# powercommander.net
KiCad netlist of a schematic drawn in EAGLE
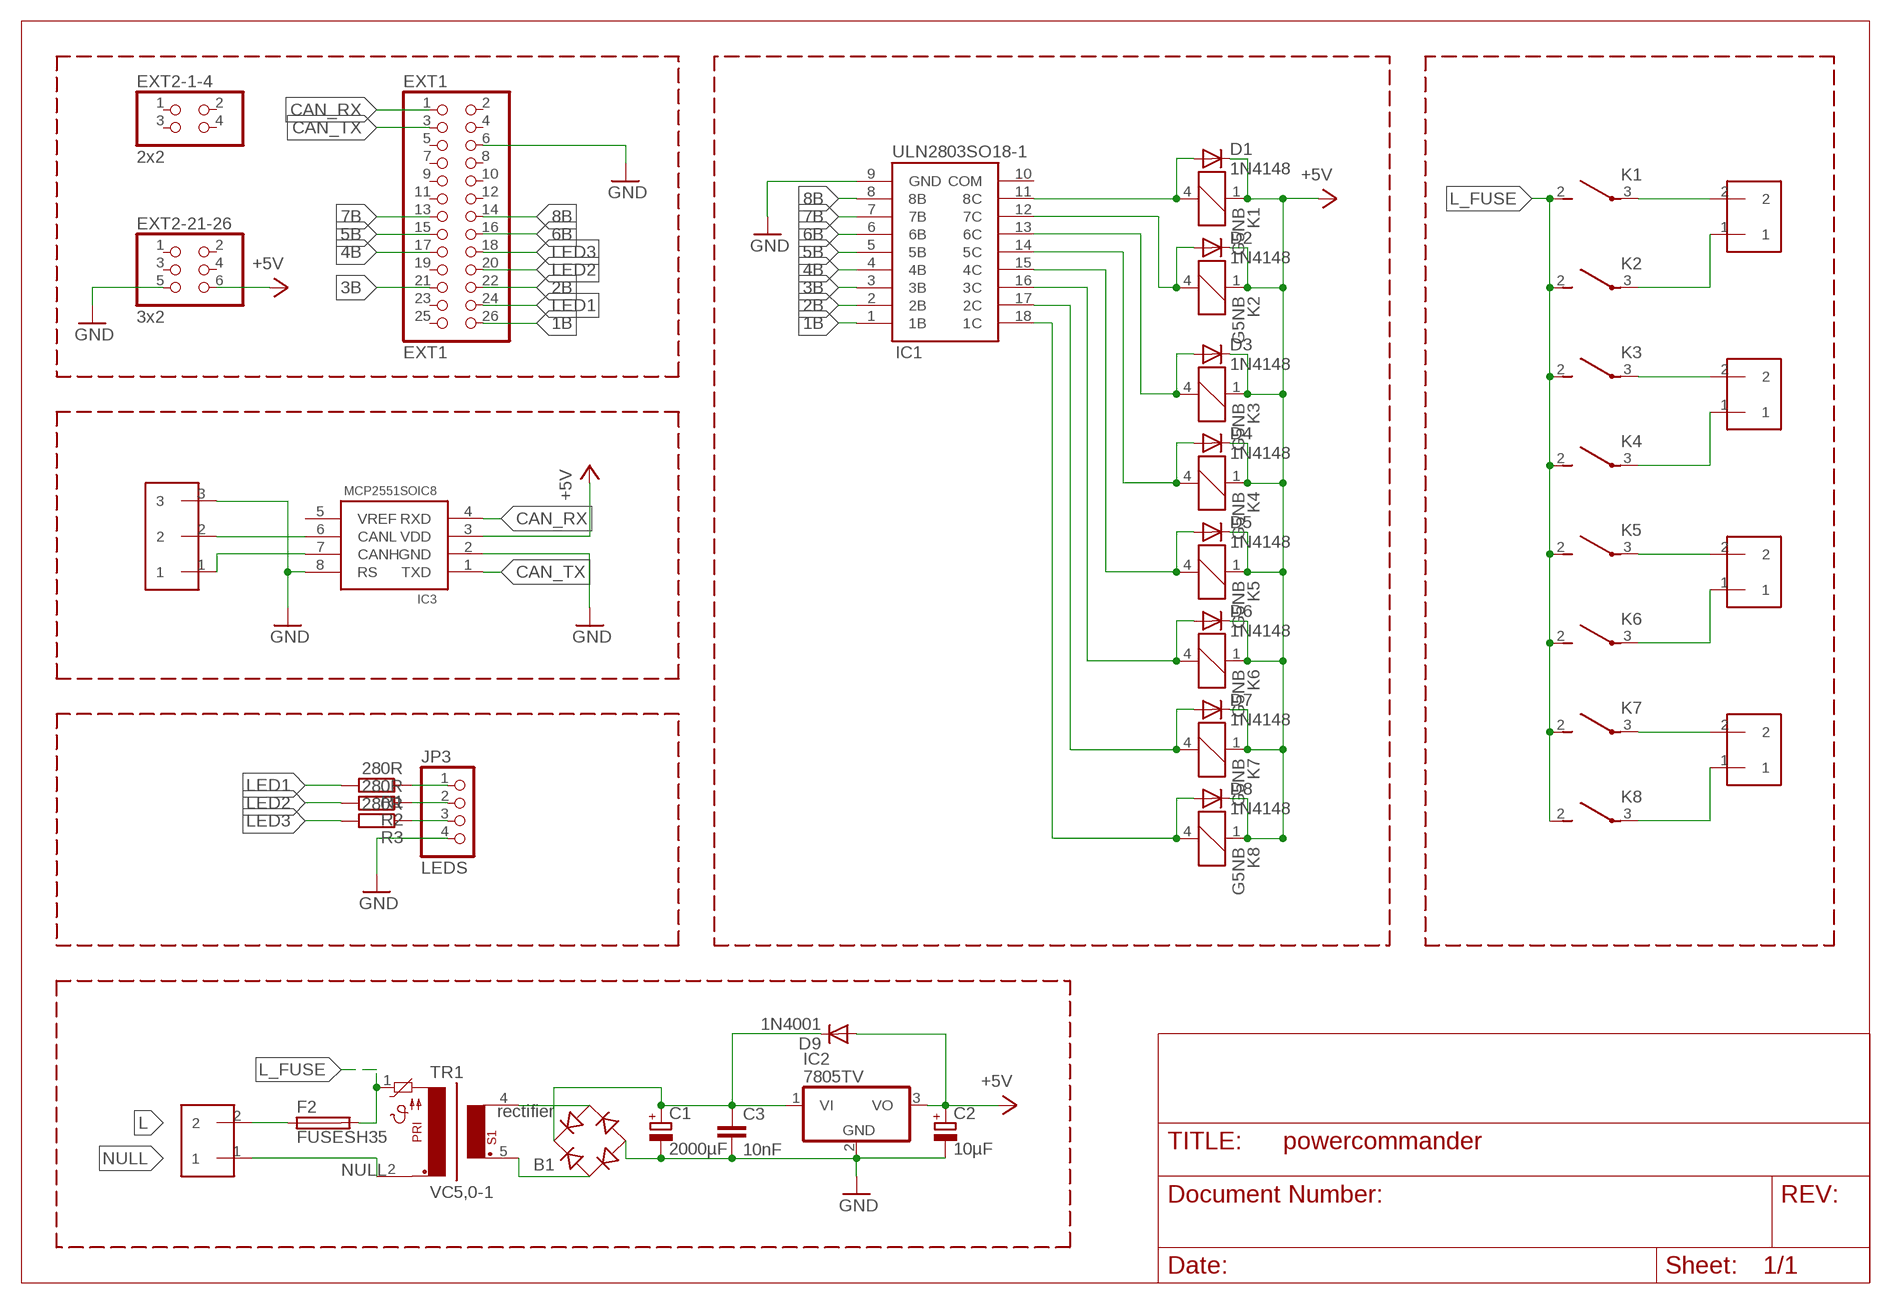
[diagram p0: schematic, sheet 1]

(export (version "E")
  (design (tool "Eeschema 10.0.6"))
  (components
    (comp (ref "B1")
      (value "rectifier")
      (footprint "eagle-import:RB1A")
      (libsource (lib "eagle-import") (part "RB1A"))
    )
    (comp (ref "C1")
      (value "2000µF")
      (footprint "eagle-import:E5-8,5")
      (libsource (lib "eagle-import") (part "CPOL-EUE5-8.5"))
    )
    (comp (ref "C2")
      (value "10µF")
      (footprint "eagle-import:E5-8,5")
      (libsource (lib "eagle-import") (part "CPOL-EUE5-8.5"))
    )
    (comp (ref "C3")
      (value "10nF")
      (footprint "eagle-import:C025-025X050")
      (libsource (lib "eagle-import") (part "C-EU025-025X050"))
    )
    (comp (ref "D1")
      (value "1N4148")
      (footprint "eagle-import:SOD323-W")
      (libsource (lib "eagle-import") (part "DIODE-SOD323-W"))
    )
    (comp (ref "D2")
      (value "1N4148")
      (footprint "eagle-import:SOD323-W")
      (libsource (lib "eagle-import") (part "DIODE-SOD323-W"))
    )
    (comp (ref "D3")
      (value "1N4148")
      (footprint "eagle-import:SOD323-W")
      (libsource (lib "eagle-import") (part "DIODE-SOD323-W"))
    )
    (comp (ref "D4")
      (value "1N4148")
      (footprint "eagle-import:SOD323-W")
      (libsource (lib "eagle-import") (part "DIODE-SOD323-W"))
    )
    (comp (ref "D5")
      (value "1N4148")
      (footprint "eagle-import:SOD323-W")
      (libsource (lib "eagle-import") (part "DIODE-SOD323-W"))
    )
    (comp (ref "D6")
      (value "1N4148")
      (footprint "eagle-import:SOD323-W")
      (libsource (lib "eagle-import") (part "DIODE-SOD323-W"))
    )
    (comp (ref "D7")
      (value "1N4148")
      (footprint "eagle-import:SOD323-W")
      (libsource (lib "eagle-import") (part "DIODE-SOD323-W"))
    )
    (comp (ref "D8")
      (value "1N4148")
      (footprint "eagle-import:SOD323-W")
      (libsource (lib "eagle-import") (part "DIODE-SOD323-W"))
    )
    (comp (ref "D9")
      (value "1N4001")
      (footprint "eagle-import:MELF-MLL41")
      (libsource (lib "eagle-import") (part "DIODE-MELF-MLL41"))
    )
    (comp (ref "EXT1")
      (value "EXT1")
      (footprint "eagle-import:2X13")
      (libsource (lib "eagle-import") (part "PINHD-2X13"))
    )
    (comp (ref "EXT2-1-4")
      (value "2x2")
      (footprint "eagle-import:2X02")
      (libsource (lib "eagle-import") (part "PINHD-2X2"))
    )
    (comp (ref "EXT2-21-26")
      (value "3x2")
      (footprint "eagle-import:2X03")
      (libsource (lib "eagle-import") (part "PINHD-2X3"))
    )
    (comp (ref "F2")
      (value "FUSESH35")
      (footprint "eagle-import:SH25")
      (libsource (lib "eagle-import") (part "FUSESH35"))
    )
    (comp (ref "IC1")
      (value "ULN2803SO18-1")
      (footprint "eagle-import:SO18-1")
      (libsource (lib "eagle-import") (part "ULN2803SO18-1"))
    )
    (comp (ref "IC2")
      (value "7805TV")
      (footprint "eagle-import:TO220V")
      (libsource (lib "eagle-import") (part "78TV05"))
    )
    (comp (ref "IC3")
      (value "MCP2551SOIC8")
      (footprint "eagle-import:SOIC-08LG")
      (libsource (lib "eagle-import") (part "MCP2551SOIC8"))
    )
    (comp (ref "JP3")
      (value "LEDS")
      (footprint "eagle-import:1X04")
      (libsource (lib "eagle-import") (part "PINHD-1X4"))
    )
    (comp (ref "K1")
      (value "G5NB")
      (footprint "eagle-import:G5NB")
      (libsource (lib "eagle-import") (part "G5NB"))
    )
    (comp (ref "K2")
      (value "G5NB")
      (footprint "eagle-import:G5NB")
      (libsource (lib "eagle-import") (part "G5NB"))
    )
    (comp (ref "K3")
      (value "G5NB")
      (footprint "eagle-import:G5NB")
      (libsource (lib "eagle-import") (part "G5NB"))
    )
    (comp (ref "K4")
      (value "G5NB")
      (footprint "eagle-import:G5NB")
      (libsource (lib "eagle-import") (part "G5NB"))
    )
    (comp (ref "K5")
      (value "G5NB")
      (footprint "eagle-import:G5NB")
      (libsource (lib "eagle-import") (part "G5NB"))
    )
    (comp (ref "K6")
      (value "G5NB")
      (footprint "eagle-import:G5NB")
      (libsource (lib "eagle-import") (part "G5NB"))
    )
    (comp (ref "K7")
      (value "G5NB")
      (footprint "eagle-import:G5NB")
      (libsource (lib "eagle-import") (part "G5NB"))
    )
    (comp (ref "K8")
      (value "G5NB")
      (footprint "eagle-import:G5NB")
      (libsource (lib "eagle-import") (part "G5NB"))
    )
    (comp (ref "PHASE")
      (value "2KLEMME")
      (footprint "eagle-import:W237-102")
      (libsource (lib "eagle-import") (part "2KLEMME"))
    )
    (comp (ref "R1")
      (value "280R")
      (footprint "eagle-import:0204_7")
      (libsource (lib "eagle-import") (part "R-EU_0204/7"))
    )
    (comp (ref "R2")
      (value "280R")
      (footprint "eagle-import:0204_7")
      (libsource (lib "eagle-import") (part "R-EU_0204/7"))
    )
    (comp (ref "R3")
      (value "280R")
      (footprint "eagle-import:0204_7")
      (libsource (lib "eagle-import") (part "R-EU_0204/7"))
    )
    (comp (ref "TR1")
      (value "VC5,0-1")
      (footprint "eagle-import:VC5,0-1")
      (libsource (lib "eagle-import") (part "VC5,0-1"))
    )
    (comp (ref "X2")
      (value "3KLEMME")
      (footprint "eagle-import:W237-103")
      (libsource (lib "eagle-import") (part "3KLEMME"))
    )
    (comp (ref "X3")
      (value "2KLEMME")
      (footprint "eagle-import:W237-102")
      (libsource (lib "eagle-import") (part "2KLEMME"))
    )
    (comp (ref "X4")
      (value "2KLEMME")
      (footprint "eagle-import:W237-102")
      (libsource (lib "eagle-import") (part "2KLEMME"))
    )
    (comp (ref "X5")
      (value "2KLEMME")
      (footprint "eagle-import:W237-102")
      (libsource (lib "eagle-import") (part "2KLEMME"))
    )
    (comp (ref "X6")
      (value "2KLEMME")
      (footprint "eagle-import:W237-102")
      (libsource (lib "eagle-import") (part "2KLEMME"))
    )
  )
  (nets
    (net (code "1") (name "+5V") (class "Default")
      (node (ref "C2") (pin "+") (pinfunction "+_+") (pintype "passive"))
      (node (ref "D1") (pin "C") (pinfunction "C_C") (pintype "passive"))
      (node (ref "D2") (pin "C") (pinfunction "C_C") (pintype "passive"))
      (node (ref "D3") (pin "C") (pinfunction "C_C") (pintype "passive"))
      (node (ref "D4") (pin "C") (pinfunction "C_C") (pintype "passive"))
      (node (ref "D5") (pin "C") (pinfunction "C_C") (pintype "passive"))
      (node (ref "D6") (pin "C") (pinfunction "C_C") (pintype "passive"))
      (node (ref "D7") (pin "C") (pinfunction "C_C") (pintype "passive"))
      (node (ref "D8") (pin "C") (pinfunction "C_C") (pintype "passive"))
      (node (ref "D9") (pin "A") (pinfunction "A_A") (pintype "passive"))
      (node (ref "EXT2-21-26") (pin "6") (pinfunction "6_6") (pintype "passive"))
      (node (ref "IC2") (pin "3") (pinfunction "VO_3") (pintype "passive"))
      (node (ref "IC3") (pin "3") (pinfunction "VDD_3") (pintype "bidirectional"))
      (node (ref "K1") (pin "1") (pinfunction "1_1") (pintype "passive"))
      (node (ref "K2") (pin "1") (pinfunction "1_1") (pintype "passive"))
      (node (ref "K3") (pin "1") (pinfunction "1_1") (pintype "passive"))
      (node (ref "K4") (pin "1") (pinfunction "1_1") (pintype "passive"))
      (node (ref "K5") (pin "1") (pinfunction "1_1") (pintype "passive"))
      (node (ref "K6") (pin "1") (pinfunction "1_1") (pintype "passive"))
      (node (ref "K7") (pin "1") (pinfunction "1_1") (pintype "passive"))
      (node (ref "K8") (pin "1") (pinfunction "1_1") (pintype "passive"))
    )
    (net (code "2") (name "1B") (class "Default")
      (node (ref "EXT1") (pin "26") (pinfunction "26_26") (pintype "passive"))
      (node (ref "IC1") (pin "1") (pinfunction "1B_1") (pintype "bidirectional"))
    )
    (net (code "3") (name "2B") (class "Default")
      (node (ref "EXT1") (pin "22") (pinfunction "22_22") (pintype "passive"))
      (node (ref "IC1") (pin "2") (pinfunction "2B_2") (pintype "bidirectional"))
    )
    (net (code "4") (name "3B") (class "Default")
      (node (ref "EXT1") (pin "21") (pinfunction "21_21") (pintype "passive"))
      (node (ref "IC1") (pin "3") (pinfunction "3B_3") (pintype "bidirectional"))
    )
    (net (code "5") (name "4B") (class "Default")
      (node (ref "EXT1") (pin "17") (pinfunction "17_17") (pintype "passive"))
      (node (ref "IC1") (pin "4") (pinfunction "4B_4") (pintype "bidirectional"))
    )
    (net (code "6") (name "5B") (class "Default")
      (node (ref "EXT1") (pin "15") (pinfunction "15_15") (pintype "passive"))
      (node (ref "IC1") (pin "5") (pinfunction "5B_5") (pintype "bidirectional"))
    )
    (net (code "7") (name "6B") (class "Default")
      (node (ref "EXT1") (pin "16") (pinfunction "16_16") (pintype "passive"))
      (node (ref "IC1") (pin "6") (pinfunction "6B_6") (pintype "bidirectional"))
    )
    (net (code "8") (name "7B") (class "Default")
      (node (ref "EXT1") (pin "13") (pinfunction "13_13") (pintype "passive"))
      (node (ref "IC1") (pin "7") (pinfunction "7B_7") (pintype "bidirectional"))
    )
    (net (code "9") (name "8B") (class "Default")
      (node (ref "EXT1") (pin "14") (pinfunction "14_14") (pintype "passive"))
      (node (ref "IC1") (pin "8") (pinfunction "8B_8") (pintype "bidirectional"))
    )
    (net (code "10") (name "CAN_RX") (class "Default")
      (node (ref "EXT1") (pin "1") (pinfunction "1_1") (pintype "passive"))
      (node (ref "IC3") (pin "4") (pinfunction "RXD_4") (pintype "bidirectional"))
    )
    (net (code "11") (name "CAN_TX") (class "Default")
      (node (ref "EXT1") (pin "3") (pinfunction "3_3") (pintype "passive"))
      (node (ref "IC3") (pin "1") (pinfunction "TXD_1") (pintype "bidirectional"))
    )
    (net (code "12") (name "GND") (class "Default")
      (node (ref "B1") (pin "-") (pinfunction "-_-") (pintype "passive"))
      (node (ref "C1") (pin "-") (pinfunction "-_-") (pintype "passive"))
      (node (ref "C2") (pin "-") (pinfunction "-_-") (pintype "passive"))
      (node (ref "C3") (pin "2") (pinfunction "2_2") (pintype "passive"))
      (node (ref "EXT1") (pin "6") (pinfunction "6_6") (pintype "passive"))
      (node (ref "EXT2-21-26") (pin "5") (pinfunction "5_5") (pintype "passive"))
      (node (ref "IC1") (pin "9") (pinfunction "GND_9") (pintype "bidirectional"))
      (node (ref "IC2") (pin "2") (pinfunction "GND_2") (pintype "passive"))
      (node (ref "IC3") (pin "2") (pinfunction "GND_2") (pintype "bidirectional"))
      (node (ref "IC3") (pin "8") (pinfunction "RS_8") (pintype "bidirectional"))
      (node (ref "JP3") (pin "4") (pinfunction "4_4") (pintype "passive"))
      (node (ref "X2") (pin "3") (pinfunction "3_3") (pintype "bidirectional"))
    )
    (net (code "13") (name "L") (class "Default")
      (node (ref "F2") (pin "1") (pinfunction "1_1") (pintype "passive"))
      (node (ref "PHASE") (pin "2") (pinfunction "2_2") (pintype "bidirectional"))
    )
    (net (code "14") (name "LED1") (class "Default")
      (node (ref "EXT1") (pin "24") (pinfunction "24_24") (pintype "passive"))
      (node (ref "R1") (pin "2") (pinfunction "2_2") (pintype "passive"))
    )
    (net (code "15") (name "LED2") (class "Default")
      (node (ref "EXT1") (pin "20") (pinfunction "20_20") (pintype "passive"))
      (node (ref "R2") (pin "2") (pinfunction "2_2") (pintype "passive"))
    )
    (net (code "16") (name "LED3") (class "Default")
      (node (ref "EXT1") (pin "18") (pinfunction "18_18") (pintype "passive"))
      (node (ref "R3") (pin "2") (pinfunction "2_2") (pintype "passive"))
    )
    (net (code "17") (name "L_FUSE") (class "Default")
      (node (ref "F2") (pin "2") (pinfunction "2_2") (pintype "passive"))
      (node (ref "K1") (pin "2") (pinfunction "2_2") (pintype "passive"))
      (node (ref "K2") (pin "2") (pinfunction "2_2") (pintype "passive"))
      (node (ref "K3") (pin "2") (pinfunction "2_2") (pintype "passive"))
      (node (ref "K4") (pin "2") (pinfunction "2_2") (pintype "passive"))
      (node (ref "K5") (pin "2") (pinfunction "2_2") (pintype "passive"))
      (node (ref "K6") (pin "2") (pinfunction "2_2") (pintype "passive"))
      (node (ref "K7") (pin "2") (pinfunction "2_2") (pintype "passive"))
      (node (ref "K8") (pin "2") (pinfunction "2_2") (pintype "passive"))
      (node (ref "TR1") (pin "1") (pinfunction "1_1") (pintype "passive"))
    )
    (net (code "18") (name "NULL") (class "Default")
      (node (ref "PHASE") (pin "1") (pinfunction "1_1") (pintype "bidirectional"))
      (node (ref "TR1") (pin "2") (pinfunction "2_2") (pintype "passive"))
    )
    (net (code "19") (name "Net-(B1-PadAC2)") (class "Default")
      (node (ref "B1") (pin "AC2") (pinfunction "AC2_AC2") (pintype "passive"))
      (node (ref "TR1") (pin "4") (pinfunction "4_4") (pintype "passive"))
    )
    (net (code "20") (name "Net-(IC1-1C)") (class "Default")
      (node (ref "D8") (pin "A") (pinfunction "A_A") (pintype "passive"))
      (node (ref "IC1") (pin "18") (pinfunction "1C_18") (pintype "bidirectional"))
      (node (ref "K8") (pin "4") (pinfunction "4_4") (pintype "passive"))
    )
    (net (code "21") (name "Net-(IC1-2C)") (class "Default")
      (node (ref "D7") (pin "A") (pinfunction "A_A") (pintype "passive"))
      (node (ref "IC1") (pin "17") (pinfunction "2C_17") (pintype "bidirectional"))
      (node (ref "K7") (pin "4") (pinfunction "4_4") (pintype "passive"))
    )
    (net (code "22") (name "Net-(IC1-3C)") (class "Default")
      (node (ref "D6") (pin "A") (pinfunction "A_A") (pintype "passive"))
      (node (ref "IC1") (pin "16") (pinfunction "3C_16") (pintype "bidirectional"))
      (node (ref "K6") (pin "4") (pinfunction "4_4") (pintype "passive"))
    )
    (net (code "23") (name "Net-(IC1-4C)") (class "Default")
      (node (ref "D5") (pin "A") (pinfunction "A_A") (pintype "passive"))
      (node (ref "IC1") (pin "15") (pinfunction "4C_15") (pintype "bidirectional"))
      (node (ref "K5") (pin "4") (pinfunction "4_4") (pintype "passive"))
    )
    (net (code "24") (name "Net-(IC1-5C)") (class "Default")
      (node (ref "D4") (pin "A") (pinfunction "A_A") (pintype "passive"))
      (node (ref "IC1") (pin "14") (pinfunction "5C_14") (pintype "bidirectional"))
      (node (ref "K4") (pin "4") (pinfunction "4_4") (pintype "passive"))
    )
    (net (code "25") (name "Net-(IC1-6C)") (class "Default")
      (node (ref "D3") (pin "A") (pinfunction "A_A") (pintype "passive"))
      (node (ref "IC1") (pin "13") (pinfunction "6C_13") (pintype "bidirectional"))
      (node (ref "K3") (pin "4") (pinfunction "4_4") (pintype "passive"))
    )
    (net (code "26") (name "Net-(IC1-7C)") (class "Default")
      (node (ref "D2") (pin "A") (pinfunction "A_A") (pintype "passive"))
      (node (ref "IC1") (pin "12") (pinfunction "7C_12") (pintype "bidirectional"))
      (node (ref "K2") (pin "4") (pinfunction "4_4") (pintype "passive"))
    )
    (net (code "27") (name "Net-(IC1-8C)") (class "Default")
      (node (ref "D1") (pin "A") (pinfunction "A_A") (pintype "passive"))
      (node (ref "IC1") (pin "11") (pinfunction "8C_11") (pintype "bidirectional"))
      (node (ref "K1") (pin "4") (pinfunction "4_4") (pintype "passive"))
    )
    (net (code "28") (name "Net-(IC2-VI)") (class "Default")
      (node (ref "B1") (pin "+") (pinfunction "+_+") (pintype "passive"))
      (node (ref "C1") (pin "+") (pinfunction "+_+") (pintype "passive"))
      (node (ref "C3") (pin "1") (pinfunction "1_1") (pintype "passive"))
      (node (ref "D9") (pin "C") (pinfunction "C_C") (pintype "passive"))
      (node (ref "IC2") (pin "1") (pinfunction "VI_1") (pintype "input"))
    )
    (net (code "29") (name "Net-(IC3-CANH)") (class "Default")
      (node (ref "IC3") (pin "7") (pinfunction "CANH_7") (pintype "bidirectional"))
      (node (ref "X2") (pin "1") (pinfunction "1_1") (pintype "bidirectional"))
    )
    (net (code "30") (name "Net-(IC3-CANL)") (class "Default")
      (node (ref "IC3") (pin "6") (pinfunction "CANL_6") (pintype "bidirectional"))
      (node (ref "X2") (pin "2") (pinfunction "2_2") (pintype "bidirectional"))
    )
    (net (code "31") (name "Net-(JP3-Pad1)") (class "Default")
      (node (ref "JP3") (pin "1") (pinfunction "1_1") (pintype "passive"))
      (node (ref "R1") (pin "1") (pinfunction "1_1") (pintype "passive"))
    )
    (net (code "32") (name "Net-(JP3-Pad2)") (class "Default")
      (node (ref "JP3") (pin "2") (pinfunction "2_2") (pintype "passive"))
      (node (ref "R2") (pin "1") (pinfunction "1_1") (pintype "passive"))
    )
    (net (code "33") (name "Net-(JP3-Pad3)") (class "Default")
      (node (ref "JP3") (pin "3") (pinfunction "3_3") (pintype "passive"))
      (node (ref "R3") (pin "1") (pinfunction "1_1") (pintype "passive"))
    )
    (net (code "34") (name "Net-(K1-Pad3)") (class "Default")
      (node (ref "K1") (pin "3") (pinfunction "3_3") (pintype "passive"))
      (node (ref "X3") (pin "2") (pinfunction "2_2") (pintype "bidirectional"))
    )
    (net (code "35") (name "Net-(K2-Pad3)") (class "Default")
      (node (ref "K2") (pin "3") (pinfunction "3_3") (pintype "passive"))
      (node (ref "X3") (pin "1") (pinfunction "1_1") (pintype "bidirectional"))
    )
    (net (code "36") (name "Net-(K3-Pad3)") (class "Default")
      (node (ref "K3") (pin "3") (pinfunction "3_3") (pintype "passive"))
      (node (ref "X4") (pin "2") (pinfunction "2_2") (pintype "bidirectional"))
    )
    (net (code "37") (name "Net-(K4-Pad3)") (class "Default")
      (node (ref "K4") (pin "3") (pinfunction "3_3") (pintype "passive"))
      (node (ref "X4") (pin "1") (pinfunction "1_1") (pintype "bidirectional"))
    )
    (net (code "38") (name "Net-(K5-Pad3)") (class "Default")
      (node (ref "K5") (pin "3") (pinfunction "3_3") (pintype "passive"))
      (node (ref "X5") (pin "2") (pinfunction "2_2") (pintype "bidirectional"))
    )
    (net (code "39") (name "Net-(K6-Pad3)") (class "Default")
      (node (ref "K6") (pin "3") (pinfunction "3_3") (pintype "passive"))
      (node (ref "X5") (pin "1") (pinfunction "1_1") (pintype "bidirectional"))
    )
    (net (code "40") (name "Net-(K7-Pad3)") (class "Default")
      (node (ref "K7") (pin "3") (pinfunction "3_3") (pintype "passive"))
      (node (ref "X6") (pin "2") (pinfunction "2_2") (pintype "bidirectional"))
    )
    (net (code "41") (name "Net-(K8-Pad3)") (class "Default")
      (node (ref "K8") (pin "3") (pinfunction "3_3") (pintype "passive"))
      (node (ref "X6") (pin "1") (pinfunction "1_1") (pintype "bidirectional"))
    )
    (net (code "42") (name "Net-(TR1-3)") (class "Default")
      (node (ref "B1") (pin "AC1") (pinfunction "AC1_AC1") (pintype "passive"))
      (node (ref "TR1") (pin "5") (pinfunction "3_5") (pintype "passive"))
    )
    (net (code "43") (name "unconnected-(EXT1-Pad2)") (class "Default")
      (node (ref "EXT1") (pin "2") (pinfunction "2_2") (pintype "passive"))
    )
    (net (code "44") (name "unconnected-(EXT1-Pad4)") (class "Default")
      (node (ref "EXT1") (pin "4") (pinfunction "4_4") (pintype "passive"))
    )
    (net (code "45") (name "unconnected-(EXT1-Pad5)") (class "Default")
      (node (ref "EXT1") (pin "5") (pinfunction "5_5") (pintype "passive"))
    )
    (net (code "46") (name "unconnected-(EXT1-Pad7)") (class "Default")
      (node (ref "EXT1") (pin "7") (pinfunction "7_7") (pintype "passive"))
    )
    (net (code "47") (name "unconnected-(EXT1-Pad8)") (class "Default")
      (node (ref "EXT1") (pin "8") (pinfunction "8_8") (pintype "passive"))
    )
    (net (code "48") (name "unconnected-(EXT1-Pad9)") (class "Default")
      (node (ref "EXT1") (pin "9") (pinfunction "9_9") (pintype "passive"))
    )
    (net (code "49") (name "unconnected-(EXT1-Pad10)") (class "Default")
      (node (ref "EXT1") (pin "10") (pinfunction "10_10") (pintype "passive"))
    )
    (net (code "50") (name "unconnected-(EXT1-Pad11)") (class "Default")
      (node (ref "EXT1") (pin "11") (pinfunction "11_11") (pintype "passive"))
    )
    (net (code "51") (name "unconnected-(EXT1-Pad12)") (class "Default")
      (node (ref "EXT1") (pin "12") (pinfunction "12_12") (pintype "passive"))
    )
    (net (code "52") (name "unconnected-(EXT1-Pad19)") (class "Default")
      (node (ref "EXT1") (pin "19") (pinfunction "19_19") (pintype "passive"))
    )
    (net (code "53") (name "unconnected-(EXT1-Pad23)") (class "Default")
      (node (ref "EXT1") (pin "23") (pinfunction "23_23") (pintype "passive"))
    )
    (net (code "54") (name "unconnected-(EXT1-Pad25)") (class "Default")
      (node (ref "EXT1") (pin "25") (pinfunction "25_25") (pintype "passive"))
    )
    (net (code "55") (name "unconnected-(EXT2-1-4-Pad1)") (class "Default")
      (node (ref "EXT2-1-4") (pin "1") (pinfunction "1_1") (pintype "passive"))
    )
    (net (code "56") (name "unconnected-(EXT2-1-4-Pad2)") (class "Default")
      (node (ref "EXT2-1-4") (pin "2") (pinfunction "2_2") (pintype "passive"))
    )
    (net (code "57") (name "unconnected-(EXT2-1-4-Pad3)") (class "Default")
      (node (ref "EXT2-1-4") (pin "3") (pinfunction "3_3") (pintype "passive"))
    )
    (net (code "58") (name "unconnected-(EXT2-1-4-Pad4)") (class "Default")
      (node (ref "EXT2-1-4") (pin "4") (pinfunction "4_4") (pintype "passive"))
    )
    (net (code "59") (name "unconnected-(EXT2-21-26-Pad1)") (class "Default")
      (node (ref "EXT2-21-26") (pin "1") (pinfunction "1_1") (pintype "passive"))
    )
    (net (code "60") (name "unconnected-(EXT2-21-26-Pad2)") (class "Default")
      (node (ref "EXT2-21-26") (pin "2") (pinfunction "2_2") (pintype "passive"))
    )
    (net (code "61") (name "unconnected-(EXT2-21-26-Pad3)") (class "Default")
      (node (ref "EXT2-21-26") (pin "3") (pinfunction "3_3") (pintype "passive"))
    )
    (net (code "62") (name "unconnected-(EXT2-21-26-Pad4)") (class "Default")
      (node (ref "EXT2-21-26") (pin "4") (pinfunction "4_4") (pintype "passive"))
    )
    (net (code "63") (name "unconnected-(IC1-COM-Pad10)") (class "Default")
      (node (ref "IC1") (pin "10") (pinfunction "COM_10") (pintype "bidirectional"))
    )
    (net (code "64") (name "unconnected-(IC3-VREF-Pad5)") (class "Default")
      (node (ref "IC3") (pin "5") (pinfunction "VREF_5") (pintype "bidirectional"))
    )
  )
)
